# MOSFET.net
KiCad netlist of a schematic drawn in Altium Designer
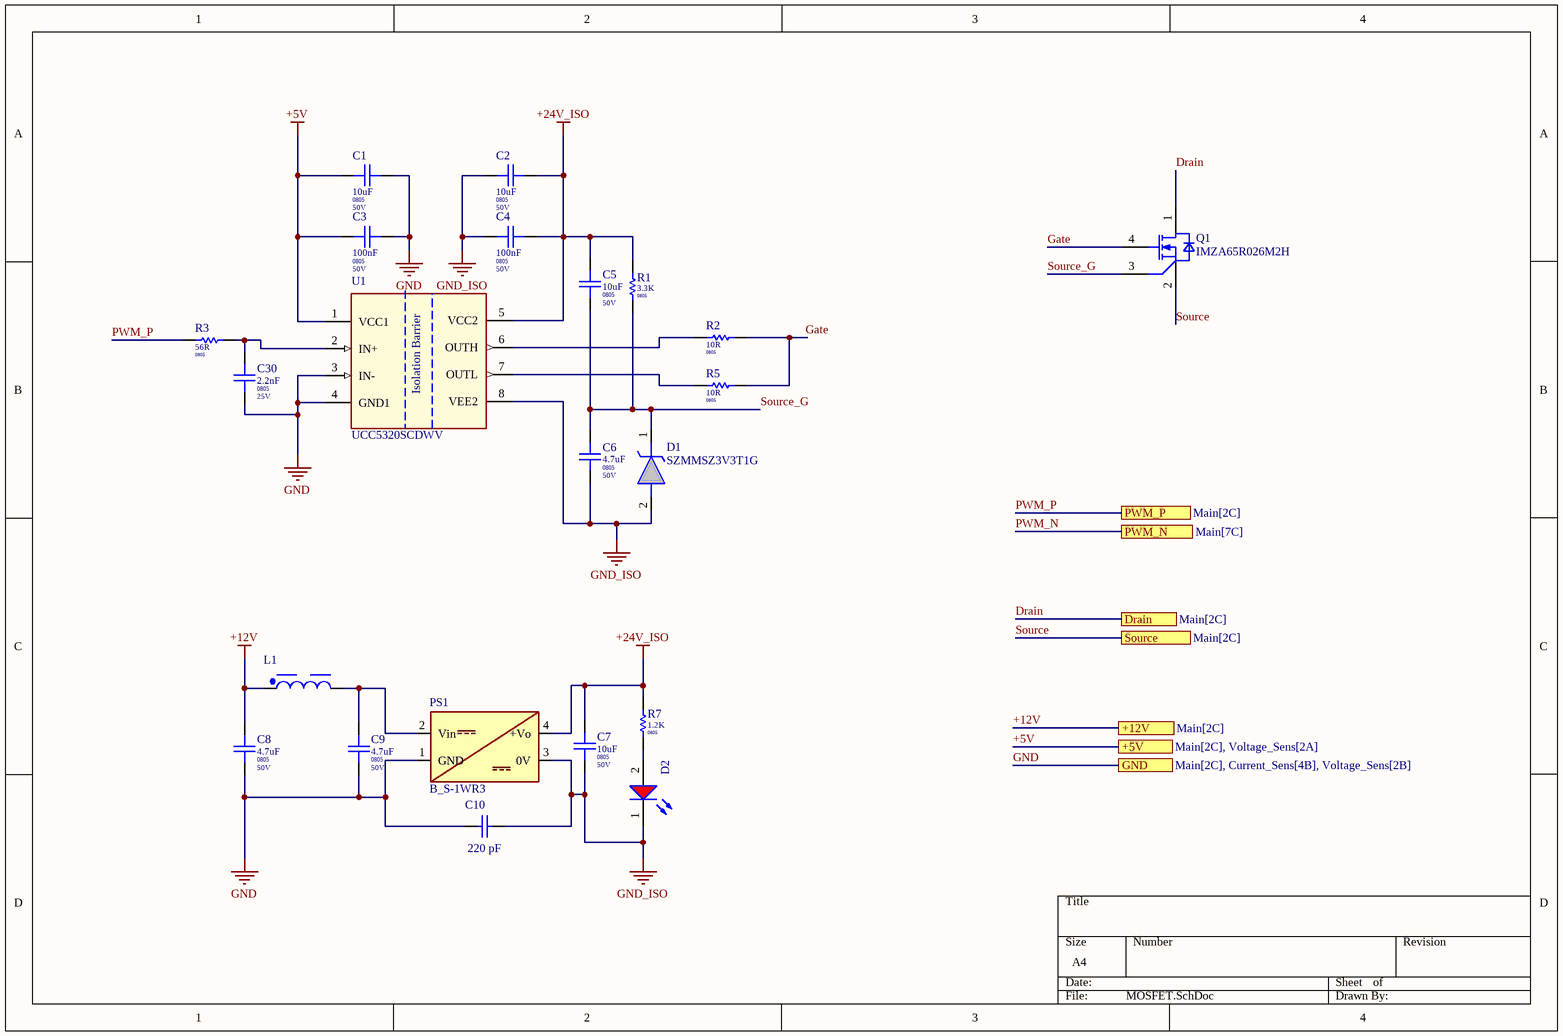
[diagram p0: MOSFET.SchDoc]

(export (version "E")
  (design (tool "Eeschema 10.0.6"))
  (components
    (comp (ref "C1")
      (value "10uF")
      (footprint "CAPC 0805")
      (description "Capacitor Ceramic 10uF 50V 0805")
      (fields
        (field (name "TOLERANCE") "%10")
        (field (name "PACKAGE / CASE") "0805")
        (field (name "VOLTAGE") "50V")
        (field (name "PART NUMBER") "CAPC0588")
      )
      (libsource (lib "Aesk Database Library") (part "NPCapacitor"))
    )
    (comp (ref "C2")
      (value "10uF")
      (footprint "CAPC 0805")
      (description "Capacitor Ceramic 10uF 50V 0805")
      (fields
        (field (name "TOLERANCE") "%10")
        (field (name "PACKAGE / CASE") "0805")
        (field (name "VOLTAGE") "50V")
        (field (name "PART NUMBER") "CAPC0588")
      )
      (libsource (lib "Aesk Database Library") (part "NPCapacitor"))
    )
    (comp (ref "C3")
      (value "100nF")
      (footprint "CAPC 0805")
      (description "Capacitor Ceramic 100nF 50V 0805")
      (fields
        (field (name "TOLERANCE") "%10")
        (field (name "PACKAGE / CASE") "0805")
        (field (name "VOLTAGE") "50V")
        (field (name "PART NUMBER") "CAPC0572")
      )
      (libsource (lib "Aesk Database Library") (part "NPCapacitor"))
    )
    (comp (ref "C4")
      (value "100nF")
      (footprint "CAPC 0805")
      (description "Capacitor Ceramic 100nF 50V 0805")
      (fields
        (field (name "TOLERANCE") "%10")
        (field (name "PACKAGE / CASE") "0805")
        (field (name "VOLTAGE") "50V")
        (field (name "PART NUMBER") "CAPC0572")
      )
      (libsource (lib "Aesk Database Library") (part "NPCapacitor"))
    )
    (comp (ref "C5")
      (value "10uF")
      (footprint "CAPC 0805")
      (description "Capacitor Ceramic 10uF 50V 0805")
      (fields
        (field (name "TOLERANCE") "%10")
        (field (name "PACKAGE / CASE") "0805")
        (field (name "VOLTAGE") "50V")
        (field (name "PART NUMBER") "CAPC0588")
      )
      (libsource (lib "Aesk Database Library") (part "NPCapacitor"))
    )
    (comp (ref "C6")
      (value "4.7uF")
      (footprint "CAPC 0805")
      (description "Capacitor Ceramic 4.7uF 50V 0805")
      (fields
        (field (name "TOLERANCE") "%10")
        (field (name "PACKAGE / CASE") "0805")
        (field (name "VOLTAGE") "50V")
        (field (name "PART NUMBER") "CAPC0584")
      )
      (libsource (lib "Aesk Database Library") (part "NPCapacitor"))
    )
    (comp (ref "C7")
      (value "10uF")
      (footprint "CAPC 0805")
      (description "Capacitor Ceramic 10uF 50V 0805")
      (fields
        (field (name "TOLERANCE") "%10")
        (field (name "PACKAGE / CASE") "0805")
        (field (name "VOLTAGE") "50V")
        (field (name "PART NUMBER") "CAPC0588")
      )
      (libsource (lib "Aesk Database Library") (part "NPCapacitor"))
    )
    (comp (ref "C8")
      (value "4.7uF")
      (footprint "CAPC 0805")
      (description "Capacitor Ceramic 4.7uF 50V 0805")
      (fields
        (field (name "TOLERANCE") "%10")
        (field (name "PACKAGE / CASE") "0805")
        (field (name "VOLTAGE") "50V")
        (field (name "PART NUMBER") "CAPC0584")
      )
      (libsource (lib "Aesk Database Library") (part "NPCapacitor"))
    )
    (comp (ref "C9")
      (value "4.7uF")
      (footprint "CAPC 0805")
      (description "Capacitor Ceramic 4.7uF 50V 0805")
      (fields
        (field (name "TOLERANCE") "%10")
        (field (name "PACKAGE / CASE") "0805")
        (field (name "VOLTAGE") "50V")
        (field (name "PART NUMBER") "CAPC0584")
      )
      (libsource (lib "Aesk Database Library") (part "NPCapacitor"))
    )
    (comp (ref "C10")
      (value "220 pF")
      (footprint "WCAP-CSSA_1808_8853620100181")
      (fields
        (field (name "MANUFACTURER PART NUMBER") "8853620100181")
        (field (name "MANUFACTURER") "Wurth Elektronik")
      )
      (libsource (lib "WE - Passive Components") (part "Capacitor_Non-Polarized"))
    )
    (comp (ref "C30")
      (value "2.2nF")
      (footprint "CAPC 0805")
      (description "Capacitor Ceramic 2.2nF 25V 0805")
      (fields
        (field (name "TOLERANCE") "%10")
        (field (name "PACKAGE / CASE") "0805")
        (field (name "VOLTAGE") "25V")
        (field (name "PART NUMBER") "CAPC0644")
      )
      (libsource (lib "Aesk Database Library") (part "NPCapacitor"))
    )
    (comp (ref "D1")
      (value "SZMMSZ3V3T1G")
      (footprint "SOD3716X135N")
      (fields (field (name "MOUSER PART NUMBER") "863-SZMMSZ3V3T1G"))
      (libsource (lib "Schlib1") (part "SZMMSZ3V3T1G"))
    )
    (comp (ref "D2")
      (value "Red, 2V, 140°")
      (footprint "WL-SMCW_0805_150080xx75000")
      (description "WL-SMCW Mono-color Chip LED Waterclear, SMT, size 0805, Red, 2V, 140°")
      (fields
        (field (name "MANUFACTURER PART NUMBER") "150080RS75000")
        (field (name "MANUFACTURER") "Wurth Elektronik")
      )
      (libsource (lib "WE - Optoelectronic Components") (part "LED_Red_2A-1K"))
    )
    (comp (ref "L1")
      (value "6.8μH")
      (footprint "WE-PD_6033R")
      (description "WE-PD SMT Power Inductor, size 6033R, 6.8μH, 2.3A, 100mΩ")
      (fields
        (field (name "MANUFACTURER PART NUMBER") "7447785006")
        (field (name "MANUFACTURER") "Wurth Elektronik")
      )
      (libsource (lib "WE - Passive Components") (part "Inductor - 2"))
    )
    (comp (ref "PS1") (value "B_S-1WR3") (footprint "B_S-1WR3") (libsource (lib "Schlib1") (part "B_S-1WR3")))
    (comp (ref "Q1")
      (value "IMZA65R026M2H")
      (footprint "INF-PG-TO247-4-3")
      (fields (field (name "MANUFACTURER") "Infineon Technologies"))
      (libsource (lib "Schlib2") (part "IMZA65R026M2H"))
    )
    (comp (ref "R1")
      (value "3.3K")
      (footprint "RESC 0805")
      (description "3.3K 0805")
      (fields
        (field (name "TOLERANCE") "%5")
        (field (name "POWER") "1/10W")
        (field (name "PACKAGE / CASE") "0805")
      )
      (libsource (lib "Aesk Database Library") (part "Resistor"))
    )
    (comp (ref "R2")
      (value "10R")
      (footprint "RESC 0805")
      (description "10R 0805")
      (fields
        (field (name "TOLERANCE") "%5")
        (field (name "POWER") "1/10W")
        (field (name "PACKAGE / CASE") "0805")
      )
      (libsource (lib "Aesk Database Library") (part "Resistor"))
    )
    (comp (ref "R3")
      (value "56R")
      (footprint "RESC 0805")
      (description "56R 0805")
      (fields
        (field (name "TOLERANCE") "%5")
        (field (name "POWER") "1/10W")
        (field (name "PACKAGE / CASE") "0805")
      )
      (libsource (lib "Aesk Database Library") (part "Resistor"))
    )
    (comp (ref "R5")
      (value "10R")
      (footprint "RESC 0805")
      (description "10R 0805")
      (fields
        (field (name "TOLERANCE") "%5")
        (field (name "POWER") "1/10W")
        (field (name "PACKAGE / CASE") "0805")
      )
      (libsource (lib "Aesk Database Library") (part "Resistor"))
    )
    (comp (ref "R7")
      (value "1.2K")
      (footprint "RESC 0805")
      (description "1.2K 0805")
      (fields
        (field (name "TOLERANCE") "%5")
        (field (name "POWER") "1/10W")
        (field (name "PACKAGE / CASE") "0805")
      )
      (libsource (lib "Aesk Database Library") (part "Resistor"))
    )
    (comp (ref "U1")
      (value "UCC5320SCDWV")
      (footprint "DWV0008A")
      (fields (field (name "COPYRIGHT") "Copyright (C) 2025 Ultra Librarian. All rights reserved."))
      (libsource (lib "Schlib1") (part "UCC5320SCDWV"))
    )
  )
  (nets
    (net (code "1") (name "+5V") (class "Default")
      (node (ref "C1") (pin "1") (pinfunction "1_1") (pintype "passive"))
      (node (ref "C3") (pin "1") (pinfunction "1_1") (pintype "passive"))
      (node (ref "U1") (pin "1") (pinfunction "VCC1_1") (pintype "power_in"))
    )
    (net (code "2") (name "+12V") (class "Default")
      (node (ref "C8") (pin "2") (pinfunction "2_2") (pintype "passive"))
      (node (ref "L1") (pin "1") (pinfunction "1_1") (pintype "passive"))
    )
    (net (code "3") (name "+24V_ISO") (class "Default")
      (node (ref "C2") (pin "2") (pinfunction "2_2") (pintype "passive"))
      (node (ref "C4") (pin "2") (pinfunction "2_2") (pintype "passive"))
      (node (ref "C5") (pin "2") (pinfunction "2_2") (pintype "passive"))
      (node (ref "C7") (pin "2") (pinfunction "2_2") (pintype "passive"))
      (node (ref "PS1") (pin "4") (pinfunction "+Vo_4") (pintype "passive"))
      (node (ref "R1") (pin "2") (pinfunction "2_2") (pintype "passive"))
      (node (ref "R7") (pin "2") (pinfunction "2_2") (pintype "passive"))
      (node (ref "U1") (pin "5") (pinfunction "VCC2_5") (pintype "power_in"))
    )
    (net (code "4") (name "/Drain") (class "Default")
      (node (ref "Q1") (pin "1") (pinfunction "DRAIN_1") (pintype "passive"))
    )
    (net (code "5") (name "/Gate") (class "Default")
      (node (ref "Q1") (pin "4") (pinfunction "GATE_4") (pintype "passive"))
      (node (ref "R2") (pin "2") (pinfunction "2_2") (pintype "passive"))
      (node (ref "R5") (pin "2") (pinfunction "2_2") (pintype "passive"))
    )
    (net (code "7") (name "/PWM_P") (class "Default")
      (node (ref "R3") (pin "1") (pinfunction "1_1") (pintype "passive"))
    )
    (net (code "8") (name "/Source") (class "Default")
      (node (ref "Q1") (pin "2") (pinfunction "SOURCE1_2") (pintype "passive"))
    )
    (net (code "9") (name "/Source_G") (class "Default")
      (node (ref "C5") (pin "1") (pinfunction "1_1") (pintype "passive"))
      (node (ref "C6") (pin "2") (pinfunction "2_2") (pintype "passive"))
      (node (ref "D1") (pin "1") (pinfunction "K_1") (pintype "passive"))
      (node (ref "Q1") (pin "3") (pinfunction "SOURCE2_3") (pintype "passive"))
      (node (ref "R1") (pin "1") (pinfunction "1_1") (pintype "passive"))
    )
    (net (code "10") (name "GND") (class "Default")
      (node (ref "C1") (pin "2") (pinfunction "2_2") (pintype "passive"))
      (node (ref "C10") (pin "1") (pinfunction "1_1") (pintype "passive"))
      (node (ref "C3") (pin "2") (pinfunction "2_2") (pintype "passive"))
      (node (ref "C30") (pin "1") (pinfunction "1_1") (pintype "passive"))
      (node (ref "C8") (pin "1") (pinfunction "1_1") (pintype "passive"))
      (node (ref "C9") (pin "1") (pinfunction "1_1") (pintype "passive"))
      (node (ref "PS1") (pin "1") (pinfunction "GND_1") (pintype "passive"))
      (node (ref "U1") (pin "3") (pinfunction "IN-_3") (pintype "input"))
      (node (ref "U1") (pin "4") (pinfunction "GND1_4") (pintype "power_in"))
    )
    (net (code "11") (name "GND_ISO") (class "Default")
      (node (ref "C10") (pin "2") (pinfunction "2_2") (pintype "passive"))
      (node (ref "C2") (pin "1") (pinfunction "1_1") (pintype "passive"))
      (node (ref "C4") (pin "1") (pinfunction "1_1") (pintype "passive"))
      (node (ref "C6") (pin "1") (pinfunction "1_1") (pintype "passive"))
      (node (ref "C7") (pin "1") (pinfunction "1_1") (pintype "passive"))
      (node (ref "D1") (pin "2") (pinfunction "A_2") (pintype "passive"))
      (node (ref "D2") (pin "1") (pinfunction "K_1") (pintype "passive"))
      (node (ref "PS1") (pin "3") (pinfunction "0V_3") (pintype "passive"))
      (node (ref "U1") (pin "8") (pinfunction "VEE2_8") (pintype "power_in"))
    )
    (net (code "12") (name "Net-(D2-A)") (class "Default")
      (node (ref "D2") (pin "2") (pinfunction "A_2") (pintype "passive"))
      (node (ref "R7") (pin "1") (pinfunction "1_1") (pintype "passive"))
    )
    (net (code "13") (name "Net-(PS1-Vin)") (class "Default")
      (node (ref "C9") (pin "2") (pinfunction "2_2") (pintype "passive"))
      (node (ref "L1") (pin "2") (pinfunction "2_2") (pintype "passive"))
      (node (ref "PS1") (pin "2") (pinfunction "Vin_2") (pintype "passive"))
    )
    (net (code "14") (name "Net-(U1-IN+)") (class "Default")
      (node (ref "C30") (pin "2") (pinfunction "2_2") (pintype "passive"))
      (node (ref "R3") (pin "2") (pinfunction "2_2") (pintype "passive"))
      (node (ref "U1") (pin "2") (pinfunction "IN+_2") (pintype "input"))
    )
    (net (code "15") (name "Net-(U1-OUTH)") (class "Default")
      (node (ref "R2") (pin "1") (pinfunction "1_1") (pintype "passive"))
      (node (ref "U1") (pin "6") (pinfunction "OUTH_6") (pintype "output"))
    )
    (net (code "16") (name "Net-(U1-OUTL)") (class "Default")
      (node (ref "R5") (pin "1") (pinfunction "1_1") (pintype "passive"))
      (node (ref "U1") (pin "7") (pinfunction "OUTL_7") (pintype "output"))
    )
  )
)
